# RpPicoW.net
KiCad netlist of a schematic drawn in Altium Designer
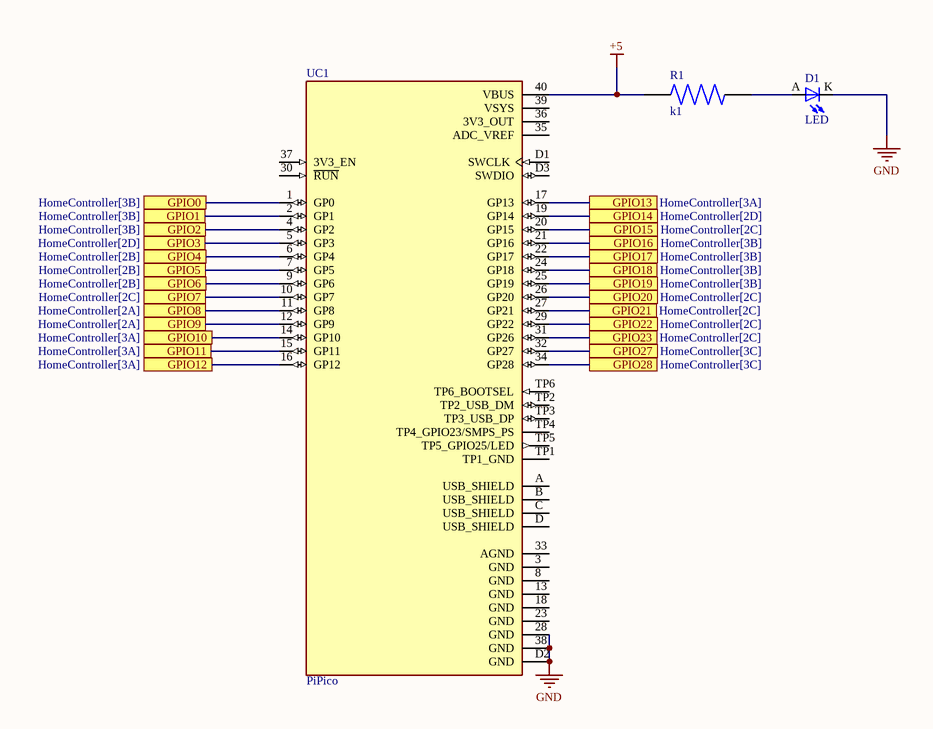
[diagram p0: RpPicoW.SchDoc]

(export (version "E")
  (design (tool "Eeschema 10.0.6"))
  (components
    (comp (ref "D1")
      (value "LED")
      (footprint "New footprint 1")
      (description "3mm LED")
      (libsource (lib "Tobias") (part "3mm LED"))
    )
    (comp (ref "R1") (value "k1") (footprint "Resistor") (libsource (lib "Basic") (part "Resistor")))
    (comp (ref "UC1") (value "PiPico") (footprint "PiPico") (libsource (lib "Components") (part "PiPico")))
  )
  (nets
    (net (code "1") (name "+5") (class "Default")
      (node (ref "R1") (pin "1") (pinfunction "1_1") (pintype "passive"))
      (node (ref "UC1") (pin "40") (pinfunction "VBUS_40") (pintype "power_in"))
    )
    (net (code "2") (name "/GPIO0") (class "Default")
      (node (ref "UC1") (pin "1") (pinfunction "GP0_1") (pintype "bidirectional"))
    )
    (net (code "3") (name "/GPIO1") (class "Default")
      (node (ref "UC1") (pin "2") (pinfunction "GP1_2") (pintype "bidirectional"))
    )
    (net (code "4") (name "/GPIO2") (class "Default")
      (node (ref "UC1") (pin "4") (pinfunction "GP2_4") (pintype "bidirectional"))
    )
    (net (code "5") (name "/GPIO3") (class "Default")
      (node (ref "UC1") (pin "5") (pinfunction "GP3_5") (pintype "bidirectional"))
    )
    (net (code "6") (name "/GPIO4") (class "Default")
      (node (ref "UC1") (pin "6") (pinfunction "GP4_6") (pintype "bidirectional"))
    )
    (net (code "7") (name "/GPIO5") (class "Default")
      (node (ref "UC1") (pin "7") (pinfunction "GP5_7") (pintype "bidirectional"))
    )
    (net (code "8") (name "/GPIO6") (class "Default")
      (node (ref "UC1") (pin "9") (pinfunction "GP6_9") (pintype "bidirectional"))
    )
    (net (code "9") (name "/GPIO7") (class "Default")
      (node (ref "UC1") (pin "10") (pinfunction "GP7_10") (pintype "bidirectional"))
    )
    (net (code "10") (name "/GPIO8") (class "Default")
      (node (ref "UC1") (pin "11") (pinfunction "GP8_11") (pintype "bidirectional"))
    )
    (net (code "11") (name "/GPIO9") (class "Default")
      (node (ref "UC1") (pin "12") (pinfunction "GP9_12") (pintype "bidirectional"))
    )
    (net (code "12") (name "/GPIO10") (class "Default")
      (node (ref "UC1") (pin "14") (pinfunction "GP10_14") (pintype "bidirectional"))
    )
    (net (code "13") (name "/GPIO11") (class "Default")
      (node (ref "UC1") (pin "15") (pinfunction "GP11_15") (pintype "bidirectional"))
    )
    (net (code "14") (name "/GPIO12") (class "Default")
      (node (ref "UC1") (pin "16") (pinfunction "GP12_16") (pintype "bidirectional"))
    )
    (net (code "15") (name "/GPIO13") (class "Default")
      (node (ref "UC1") (pin "17") (pinfunction "GP13_17") (pintype "bidirectional"))
    )
    (net (code "16") (name "/GPIO14") (class "Default")
      (node (ref "UC1") (pin "19") (pinfunction "GP14_19") (pintype "bidirectional"))
    )
    (net (code "17") (name "/GPIO15") (class "Default")
      (node (ref "UC1") (pin "20") (pinfunction "GP15_20") (pintype "bidirectional"))
    )
    (net (code "18") (name "/GPIO16") (class "Default")
      (node (ref "UC1") (pin "21") (pinfunction "GP16_21") (pintype "bidirectional"))
    )
    (net (code "19") (name "/GPIO17") (class "Default")
      (node (ref "UC1") (pin "22") (pinfunction "GP17_22") (pintype "bidirectional"))
    )
    (net (code "20") (name "/GPIO18") (class "Default")
      (node (ref "UC1") (pin "24") (pinfunction "GP18_24") (pintype "bidirectional"))
    )
    (net (code "21") (name "/GPIO19") (class "Default")
      (node (ref "UC1") (pin "25") (pinfunction "GP19_25") (pintype "bidirectional"))
    )
    (net (code "22") (name "/GPIO20") (class "Default")
      (node (ref "UC1") (pin "26") (pinfunction "GP20_26") (pintype "bidirectional"))
    )
    (net (code "23") (name "/GPIO21") (class "Default")
      (node (ref "UC1") (pin "27") (pinfunction "GP21_27") (pintype "bidirectional"))
    )
    (net (code "24") (name "/GPIO22") (class "Default")
      (node (ref "UC1") (pin "29") (pinfunction "GP22_29") (pintype "bidirectional"))
    )
    (net (code "25") (name "/GPIO23") (class "Default")
      (node (ref "UC1") (pin "31") (pinfunction "GP26_31") (pintype "bidirectional"))
    )
    (net (code "26") (name "/GPIO27") (class "Default")
      (node (ref "UC1") (pin "32") (pinfunction "GP27_32") (pintype "bidirectional"))
    )
    (net (code "27") (name "/GPIO28") (class "Default")
      (node (ref "UC1") (pin "34") (pinfunction "GP28_34") (pintype "bidirectional"))
    )
    (net (code "28") (name "GND") (class "Default")
      (node (ref "D1") (pin "K") (pinfunction "K_K") (pintype "passive"))
      (node (ref "UC1") (pin "28") (pinfunction "GND_28") (pintype "power_in"))
      (node (ref "UC1") (pin "38") (pinfunction "GND_38") (pintype "power_in"))
      (node (ref "UC1") (pin "D2") (pinfunction "GND_D2") (pintype "power_in"))
    )
    (net (code "29") (name "Net-(D1-PadA)") (class "Default")
      (node (ref "D1") (pin "A") (pinfunction "A_A") (pintype "passive"))
      (node (ref "R1") (pin "2") (pinfunction "2_2") (pintype "passive"))
    )
    (net (code "30") (name "unconnected-(UC1-3V3_EN-Pad37)") (class "Default")
      (node (ref "UC1") (pin "37") (pinfunction "3V3_EN_37") (pintype "input"))
    )
    (net (code "31") (name "unconnected-(UC1-3V3_OUT-Pad36)") (class "Default")
      (node (ref "UC1") (pin "36") (pinfunction "3V3_OUT_36") (pintype "power_in"))
    )
    (net (code "32") (name "unconnected-(UC1-ADC_VREF-Pad35)") (class "Default")
      (node (ref "UC1") (pin "35") (pinfunction "ADC_VREF_35") (pintype "power_in"))
    )
    (net (code "33") (name "unconnected-(UC1-AGND-Pad33)") (class "Default")
      (node (ref "UC1") (pin "33") (pinfunction "AGND_33") (pintype "power_in"))
    )
    (net (code "34") (name "unconnected-(UC1-GND-Pad3)") (class "Default")
      (node (ref "UC1") (pin "3") (pinfunction "GND_3") (pintype "power_in"))
    )
    (net (code "35") (name "unconnected-(UC1-GND-Pad8)") (class "Default")
      (node (ref "UC1") (pin "8") (pinfunction "GND_8") (pintype "power_in"))
    )
    (net (code "36") (name "unconnected-(UC1-GND-Pad13)") (class "Default")
      (node (ref "UC1") (pin "13") (pinfunction "GND_13") (pintype "power_in"))
    )
    (net (code "37") (name "unconnected-(UC1-GND-Pad18)") (class "Default")
      (node (ref "UC1") (pin "18") (pinfunction "GND_18") (pintype "power_in"))
    )
    (net (code "38") (name "unconnected-(UC1-GND-Pad23)") (class "Default")
      (node (ref "UC1") (pin "23") (pinfunction "GND_23") (pintype "power_in"))
    )
    (net (code "39") (name "unconnected-(UC1-SWCLK-PadD1)") (class "Default")
      (node (ref "UC1") (pin "D1") (pinfunction "SWCLK_D1") (pintype "input"))
    )
    (net (code "40") (name "unconnected-(UC1-SWDIO-PadD3)") (class "Default")
      (node (ref "UC1") (pin "D3") (pinfunction "SWDIO_D3") (pintype "bidirectional"))
    )
    (net (code "41") (name "unconnected-(UC1-TP1_GND-PadTP1)") (class "Default")
      (node (ref "UC1") (pin "TP1") (pinfunction "TP1_GND_TP1") (pintype "power_in"))
    )
    (net (code "42") (name "unconnected-(UC1-TP2_USB_DM-PadTP2)") (class "Default")
      (node (ref "UC1") (pin "TP2") (pinfunction "TP2_USB_DM_TP2") (pintype "bidirectional"))
    )
    (net (code "43") (name "unconnected-(UC1-TP3_USB_DP-PadTP3)") (class "Default")
      (node (ref "UC1") (pin "TP3") (pinfunction "TP3_USB_DP_TP3") (pintype "bidirectional"))
    )
    (net (code "44") (name "unconnected-(UC1-TP4_GPIO23{slash}SMPS_PS-PadTP4)") (class "Default")
      (node (ref "UC1") (pin "TP4") (pinfunction "TP4_GPIO23/SMPS_PS_TP4") (pintype "passive"))
    )
    (net (code "45") (name "unconnected-(UC1-TP5_GPIO25{slash}LED-PadTP5)") (class "Default")
      (node (ref "UC1") (pin "TP5") (pinfunction "TP5_GPIO25/LED_TP5") (pintype "output"))
    )
    (net (code "46") (name "unconnected-(UC1-TP6_BOOTSEL-PadTP6)") (class "Default")
      (node (ref "UC1") (pin "TP6") (pinfunction "TP6_BOOTSEL_TP6") (pintype "input"))
    )
    (net (code "47") (name "unconnected-(UC1-USB_SHIELD-PadA)") (class "Default")
      (node (ref "UC1") (pin "A") (pinfunction "USB_SHIELD_A") (pintype "power_in"))
    )
    (net (code "48") (name "unconnected-(UC1-USB_SHIELD-PadB)") (class "Default")
      (node (ref "UC1") (pin "B") (pinfunction "USB_SHIELD_B") (pintype "power_in"))
    )
    (net (code "49") (name "unconnected-(UC1-USB_SHIELD-PadC)") (class "Default")
      (node (ref "UC1") (pin "C") (pinfunction "USB_SHIELD_C") (pintype "power_in"))
    )
    (net (code "50") (name "unconnected-(UC1-USB_SHIELD-PadD)") (class "Default")
      (node (ref "UC1") (pin "D") (pinfunction "USB_SHIELD_D") (pintype "power_in"))
    )
    (net (code "51") (name "unconnected-(UC1-VSYS-Pad39)") (class "Default")
      (node (ref "UC1") (pin "39") (pinfunction "VSYS_39") (pintype "power_in"))
    )
    (net (code "52") (name "unconnected-(UC1-~{RUN}-Pad30)") (class "Default")
      (node (ref "UC1") (pin "30") (pinfunction "~{RUN}_30") (pintype "input"))
    )
  )
)
